# Piezo.net
KiCad netlist of a schematic drawn in EAGLE
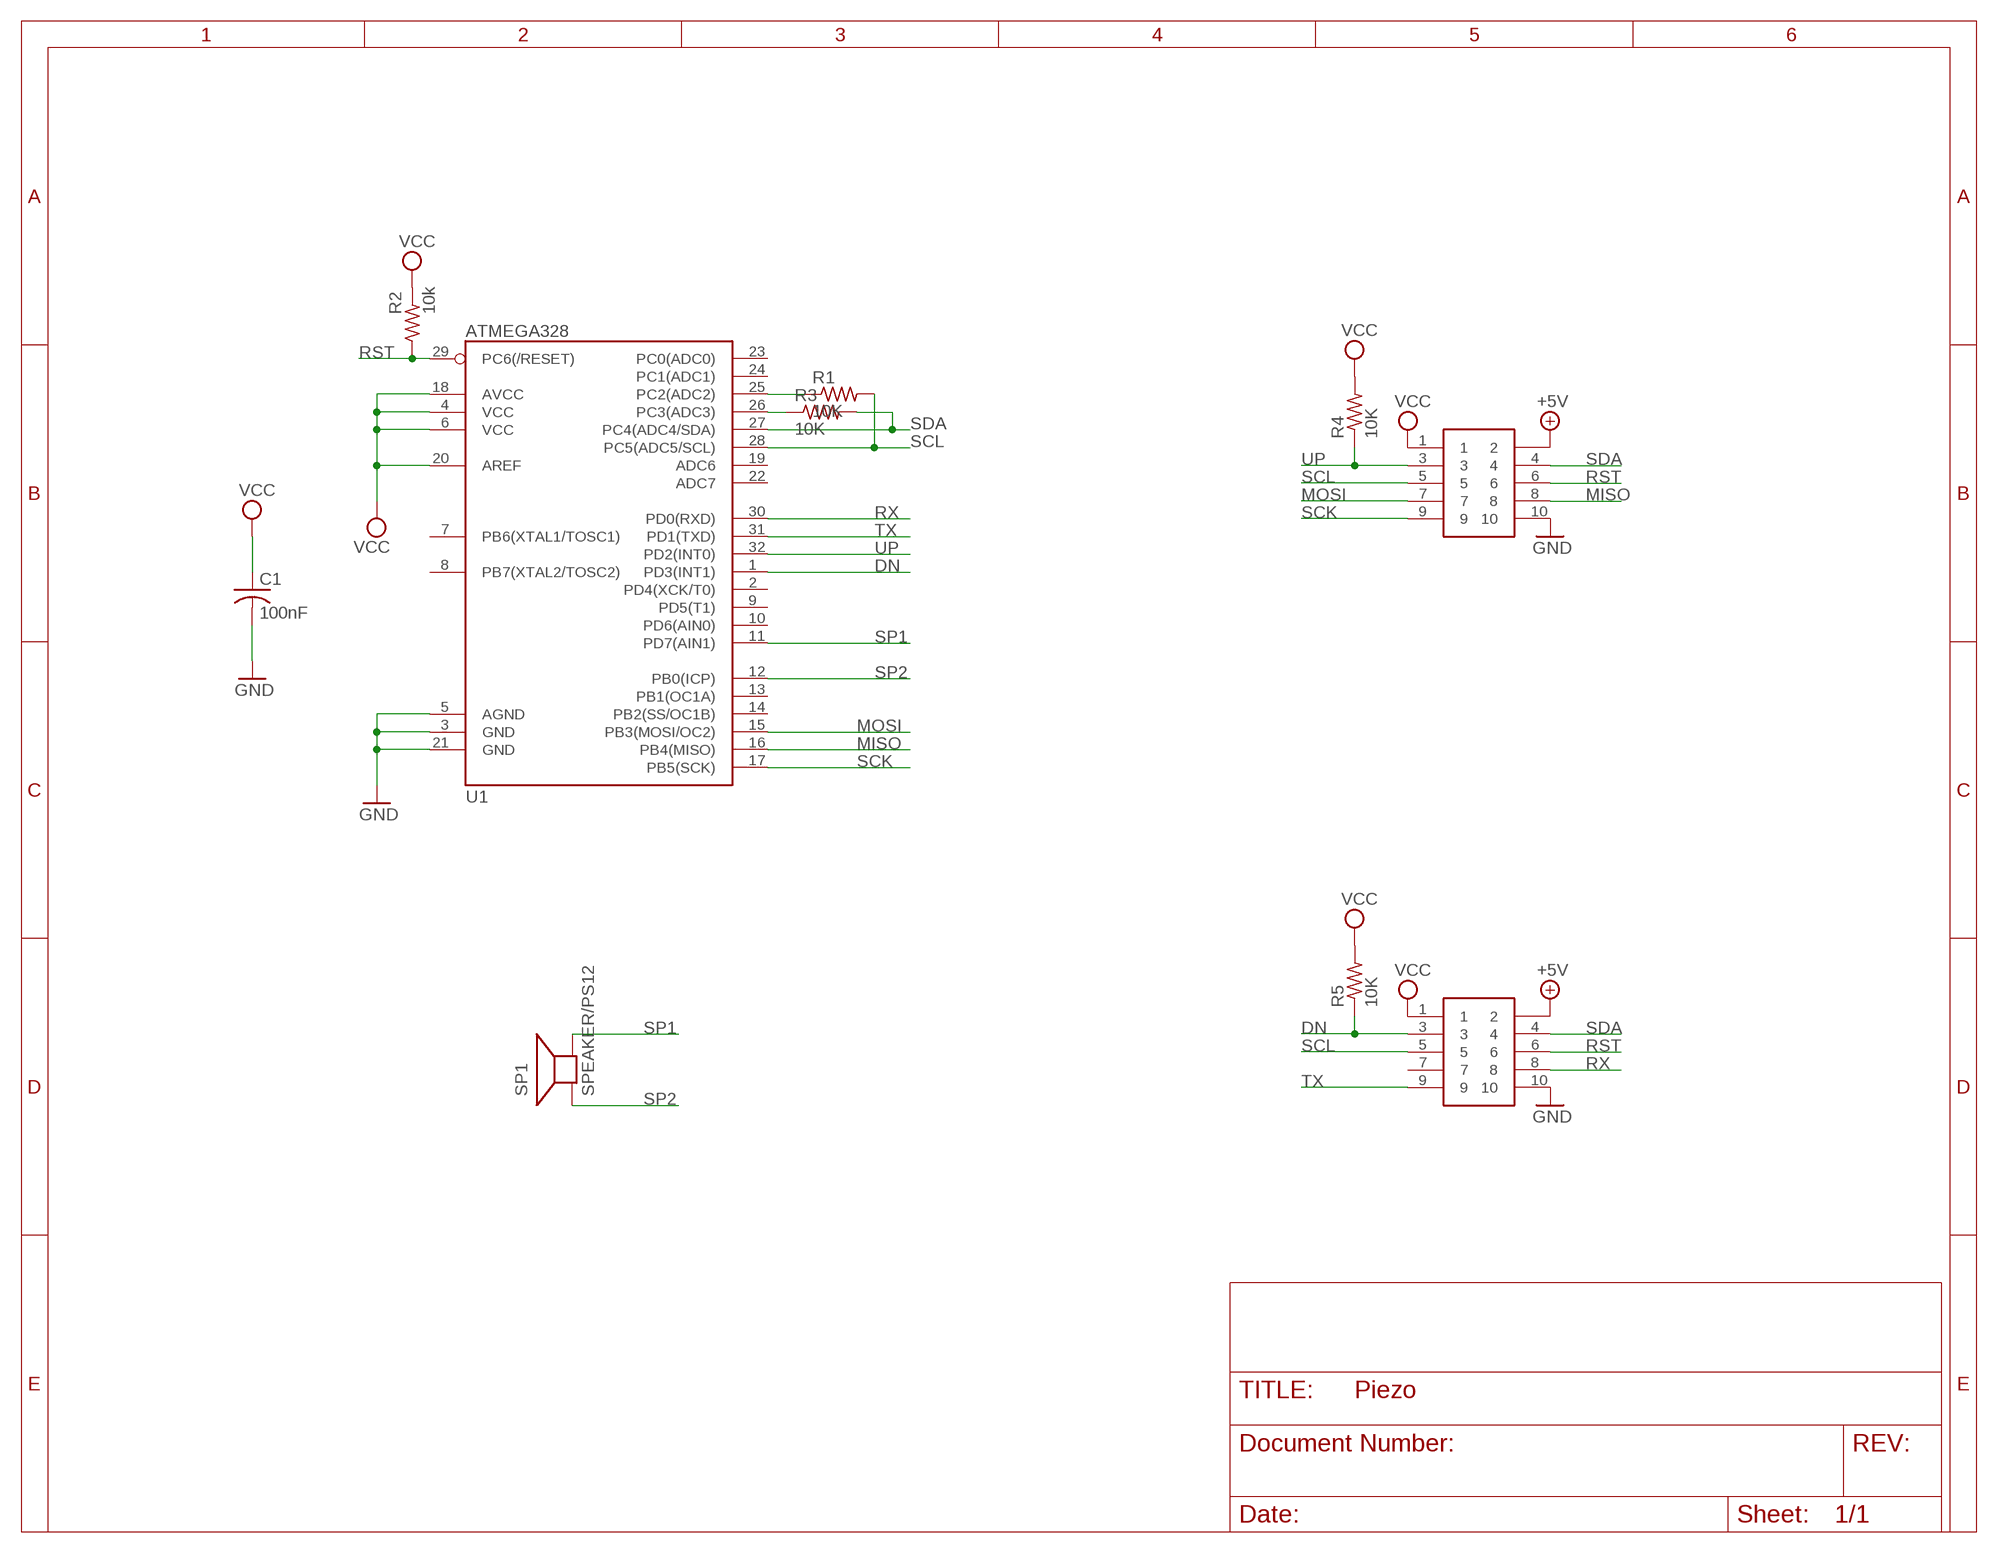
[diagram p0: schematic, sheet 1]

(export (version "E")
  (design (tool "Eeschema 10.0.6"))
  (components
    (comp (ref "*")
      (value "SHF105SM")
      (footprint "eagle-import:SHF105DSM")
      (libsource (lib "eagle-import") (part "SHF105SM"))
    )
    (comp (ref "C1")
      (value "100nF")
      (footprint "eagle-import:C0603K")
      (libsource (lib "eagle-import") (part "C-USC0603K"))
    )
    (comp (ref "R1")
      (value "10K")
      (footprint "eagle-import:R0603")
      (libsource (lib "eagle-import") (part "R-US_R0603"))
    )
    (comp (ref "R2")
      (value "10k")
      (footprint "eagle-import:R0603")
      (libsource (lib "eagle-import") (part "resistor_R-US_R0603"))
    )
    (comp (ref "R3")
      (value "10K")
      (footprint "eagle-import:R0603")
      (libsource (lib "eagle-import") (part "R-US_R0603"))
    )
    (comp (ref "R4")
      (value "10K")
      (footprint "eagle-import:R0603")
      (libsource (lib "eagle-import") (part "R-US_R0603"))
    )
    (comp (ref "R5")
      (value "10K")
      (footprint "eagle-import:R0603")
      (libsource (lib "eagle-import") (part "R-US_R0603"))
    )
    (comp (ref "SP1")
      (value "SPEAKER/PS12")
      (footprint "eagle-import:PS12")
      (libsource (lib "eagle-import") (part "SPEAKER/PS12"))
    )
    (comp (ref "U1")
      (value "ATMEGA328")
      (footprint "eagle-import:TQFP32-08")
      (libsource (lib "eagle-import") (part "ATMEGA168"))
    )
    (comp (ref "XY")
      (value "SHF105SM")
      (footprint "eagle-import:SHF105DSM")
      (libsource (lib "eagle-import") (part "SHF105SM"))
    )
  )
  (nets
    (net (code "1") (name "+5V") (class "Default")
      (node (ref "*") (pin "2") (pinfunction "2_2") (pintype "passive"))
      (node (ref "XY") (pin "2") (pinfunction "2_2") (pintype "passive"))
    )
    (net (code "2") (name "/DN") (class "Default")
      (node (ref "*") (pin "3") (pinfunction "3_3") (pintype "passive"))
      (node (ref "R5") (pin "1") (pinfunction "1_1") (pintype "passive"))
      (node (ref "U1") (pin "1") (pinfunction "PD3(INT1)_1") (pintype "bidirectional"))
    )
    (net (code "3") (name "/MISO") (class "Default")
      (node (ref "U1") (pin "16") (pinfunction "PB4(MISO)_16") (pintype "bidirectional"))
      (node (ref "XY") (pin "8") (pinfunction "8_8") (pintype "passive"))
    )
    (net (code "4") (name "/MOSI") (class "Default")
      (node (ref "U1") (pin "15") (pinfunction "PB3(MOSI/OC2)_15") (pintype "bidirectional"))
      (node (ref "XY") (pin "7") (pinfunction "7_7") (pintype "passive"))
    )
    (net (code "5") (name "/RST") (class "Default")
      (node (ref "*") (pin "6") (pinfunction "6_6") (pintype "passive"))
      (node (ref "R2") (pin "1") (pinfunction "1_1") (pintype "passive"))
      (node (ref "U1") (pin "29") (pinfunction "PC6(/RESET)_29") (pintype "bidirectional"))
      (node (ref "XY") (pin "6") (pinfunction "6_6") (pintype "passive"))
    )
    (net (code "6") (name "/RX") (class "Default")
      (node (ref "*") (pin "8") (pinfunction "8_8") (pintype "passive"))
      (node (ref "U1") (pin "30") (pinfunction "PD0(RXD)_30") (pintype "bidirectional"))
    )
    (net (code "7") (name "/SCK") (class "Default")
      (node (ref "U1") (pin "17") (pinfunction "PB5(SCK)_17") (pintype "bidirectional"))
      (node (ref "XY") (pin "9") (pinfunction "9_9") (pintype "passive"))
    )
    (net (code "8") (name "/SCL") (class "Default")
      (node (ref "*") (pin "5") (pinfunction "5_5") (pintype "passive"))
      (node (ref "R1") (pin "2") (pinfunction "2_2") (pintype "passive"))
      (node (ref "U1") (pin "28") (pinfunction "PC5(ADC5/SCL)_28") (pintype "bidirectional"))
      (node (ref "XY") (pin "5") (pinfunction "5_5") (pintype "passive"))
    )
    (net (code "9") (name "/SDA") (class "Default")
      (node (ref "*") (pin "4") (pinfunction "4_4") (pintype "passive"))
      (node (ref "R3") (pin "2") (pinfunction "2_2") (pintype "passive"))
      (node (ref "U1") (pin "27") (pinfunction "PC4(ADC4/SDA)_27") (pintype "bidirectional"))
      (node (ref "XY") (pin "4") (pinfunction "4_4") (pintype "passive"))
    )
    (net (code "10") (name "/SP1") (class "Default")
      (node (ref "SP1") (pin "P$2") (pinfunction "-_P$2") (pintype "passive"))
      (node (ref "U1") (pin "11") (pinfunction "PD7(AIN1)_11") (pintype "bidirectional"))
    )
    (net (code "11") (name "/SP2") (class "Default")
      (node (ref "SP1") (pin "P$1") (pinfunction "+_P$1") (pintype "passive"))
      (node (ref "U1") (pin "12") (pinfunction "PB0(ICP)_12") (pintype "bidirectional"))
    )
    (net (code "12") (name "/TX") (class "Default")
      (node (ref "*") (pin "9") (pinfunction "9_9") (pintype "passive"))
      (node (ref "U1") (pin "31") (pinfunction "PD1(TXD)_31") (pintype "bidirectional"))
    )
    (net (code "13") (name "/UP") (class "Default")
      (node (ref "R4") (pin "1") (pinfunction "1_1") (pintype "passive"))
      (node (ref "U1") (pin "32") (pinfunction "PD2(INT0)_32") (pintype "bidirectional"))
      (node (ref "XY") (pin "3") (pinfunction "3_3") (pintype "passive"))
    )
    (net (code "14") (name "GND") (class "Default")
      (node (ref "*") (pin "10") (pinfunction "10_10") (pintype "passive"))
      (node (ref "C1") (pin "2") (pinfunction "2_2") (pintype "passive"))
      (node (ref "U1") (pin "21") (pinfunction "GND_21") (pintype "bidirectional"))
      (node (ref "U1") (pin "3") (pinfunction "GND_3") (pintype "bidirectional"))
      (node (ref "U1") (pin "5") (pinfunction "AGND_5") (pintype "bidirectional"))
      (node (ref "XY") (pin "10") (pinfunction "10_10") (pintype "passive"))
    )
    (net (code "15") (name "Net-(U1-PC2(ADC2))") (class "Default")
      (node (ref "R1") (pin "1") (pinfunction "1_1") (pintype "passive"))
      (node (ref "U1") (pin "25") (pinfunction "PC2(ADC2)_25") (pintype "bidirectional"))
    )
    (net (code "16") (name "Net-(U1-PC3(ADC3))") (class "Default")
      (node (ref "R3") (pin "1") (pinfunction "1_1") (pintype "passive"))
      (node (ref "U1") (pin "26") (pinfunction "PC3(ADC3)_26") (pintype "bidirectional"))
    )
    (net (code "17") (name "VCC") (class "Default")
      (node (ref "*") (pin "1") (pinfunction "1_1") (pintype "passive"))
      (node (ref "C1") (pin "1") (pinfunction "1_1") (pintype "passive"))
      (node (ref "R2") (pin "2") (pinfunction "2_2") (pintype "passive"))
      (node (ref "R4") (pin "2") (pinfunction "2_2") (pintype "passive"))
      (node (ref "R5") (pin "2") (pinfunction "2_2") (pintype "passive"))
      (node (ref "U1") (pin "18") (pinfunction "AVCC_18") (pintype "bidirectional"))
      (node (ref "U1") (pin "20") (pinfunction "AREF_20") (pintype "bidirectional"))
      (node (ref "U1") (pin "4") (pinfunction "VCC_4") (pintype "bidirectional"))
      (node (ref "U1") (pin "6") (pinfunction "VCC_6") (pintype "bidirectional"))
      (node (ref "XY") (pin "1") (pinfunction "1_1") (pintype "passive"))
    )
    (net (code "18") (name "unconnected-(*-Pad7)") (class "Default")
      (node (ref "*") (pin "7") (pinfunction "7_7") (pintype "passive"))
    )
    (net (code "19") (name "unconnected-(U1-ADC6-Pad19)") (class "Default")
      (node (ref "U1") (pin "19") (pinfunction "ADC6_19") (pintype "bidirectional"))
    )
    (net (code "20") (name "unconnected-(U1-ADC7-Pad22)") (class "Default")
      (node (ref "U1") (pin "22") (pinfunction "ADC7_22") (pintype "bidirectional"))
    )
    (net (code "21") (name "unconnected-(U1-PB1(OC1A)-Pad13)") (class "Default")
      (node (ref "U1") (pin "13") (pinfunction "PB1(OC1A)_13") (pintype "bidirectional"))
    )
    (net (code "22") (name "unconnected-(U1-PB2(SS{slash}OC1B)-Pad14)") (class "Default")
      (node (ref "U1") (pin "14") (pinfunction "PB2(SS/OC1B)_14") (pintype "bidirectional"))
    )
    (net (code "23") (name "unconnected-(U1-PB6(XTAL1{slash}TOSC1)-Pad7)") (class "Default")
      (node (ref "U1") (pin "7") (pinfunction "PB6(XTAL1/TOSC1)_7") (pintype "bidirectional"))
    )
    (net (code "24") (name "unconnected-(U1-PB7(XTAL2{slash}TOSC2)-Pad8)") (class "Default")
      (node (ref "U1") (pin "8") (pinfunction "PB7(XTAL2/TOSC2)_8") (pintype "bidirectional"))
    )
    (net (code "25") (name "unconnected-(U1-PC0(ADC0)-Pad23)") (class "Default")
      (node (ref "U1") (pin "23") (pinfunction "PC0(ADC0)_23") (pintype "bidirectional"))
    )
    (net (code "26") (name "unconnected-(U1-PC1(ADC1)-Pad24)") (class "Default")
      (node (ref "U1") (pin "24") (pinfunction "PC1(ADC1)_24") (pintype "bidirectional"))
    )
    (net (code "27") (name "unconnected-(U1-PD4(XCK{slash}T0)-Pad2)") (class "Default")
      (node (ref "U1") (pin "2") (pinfunction "PD4(XCK/T0)_2") (pintype "bidirectional"))
    )
    (net (code "28") (name "unconnected-(U1-PD5(T1)-Pad9)") (class "Default")
      (node (ref "U1") (pin "9") (pinfunction "PD5(T1)_9") (pintype "bidirectional"))
    )
    (net (code "29") (name "unconnected-(U1-PD6(AIN0)-Pad10)") (class "Default")
      (node (ref "U1") (pin "10") (pinfunction "PD6(AIN0)_10") (pintype "bidirectional"))
    )
  )
)
